# untitled.net
KiCad netlist of a schematic drawn in EAGLE
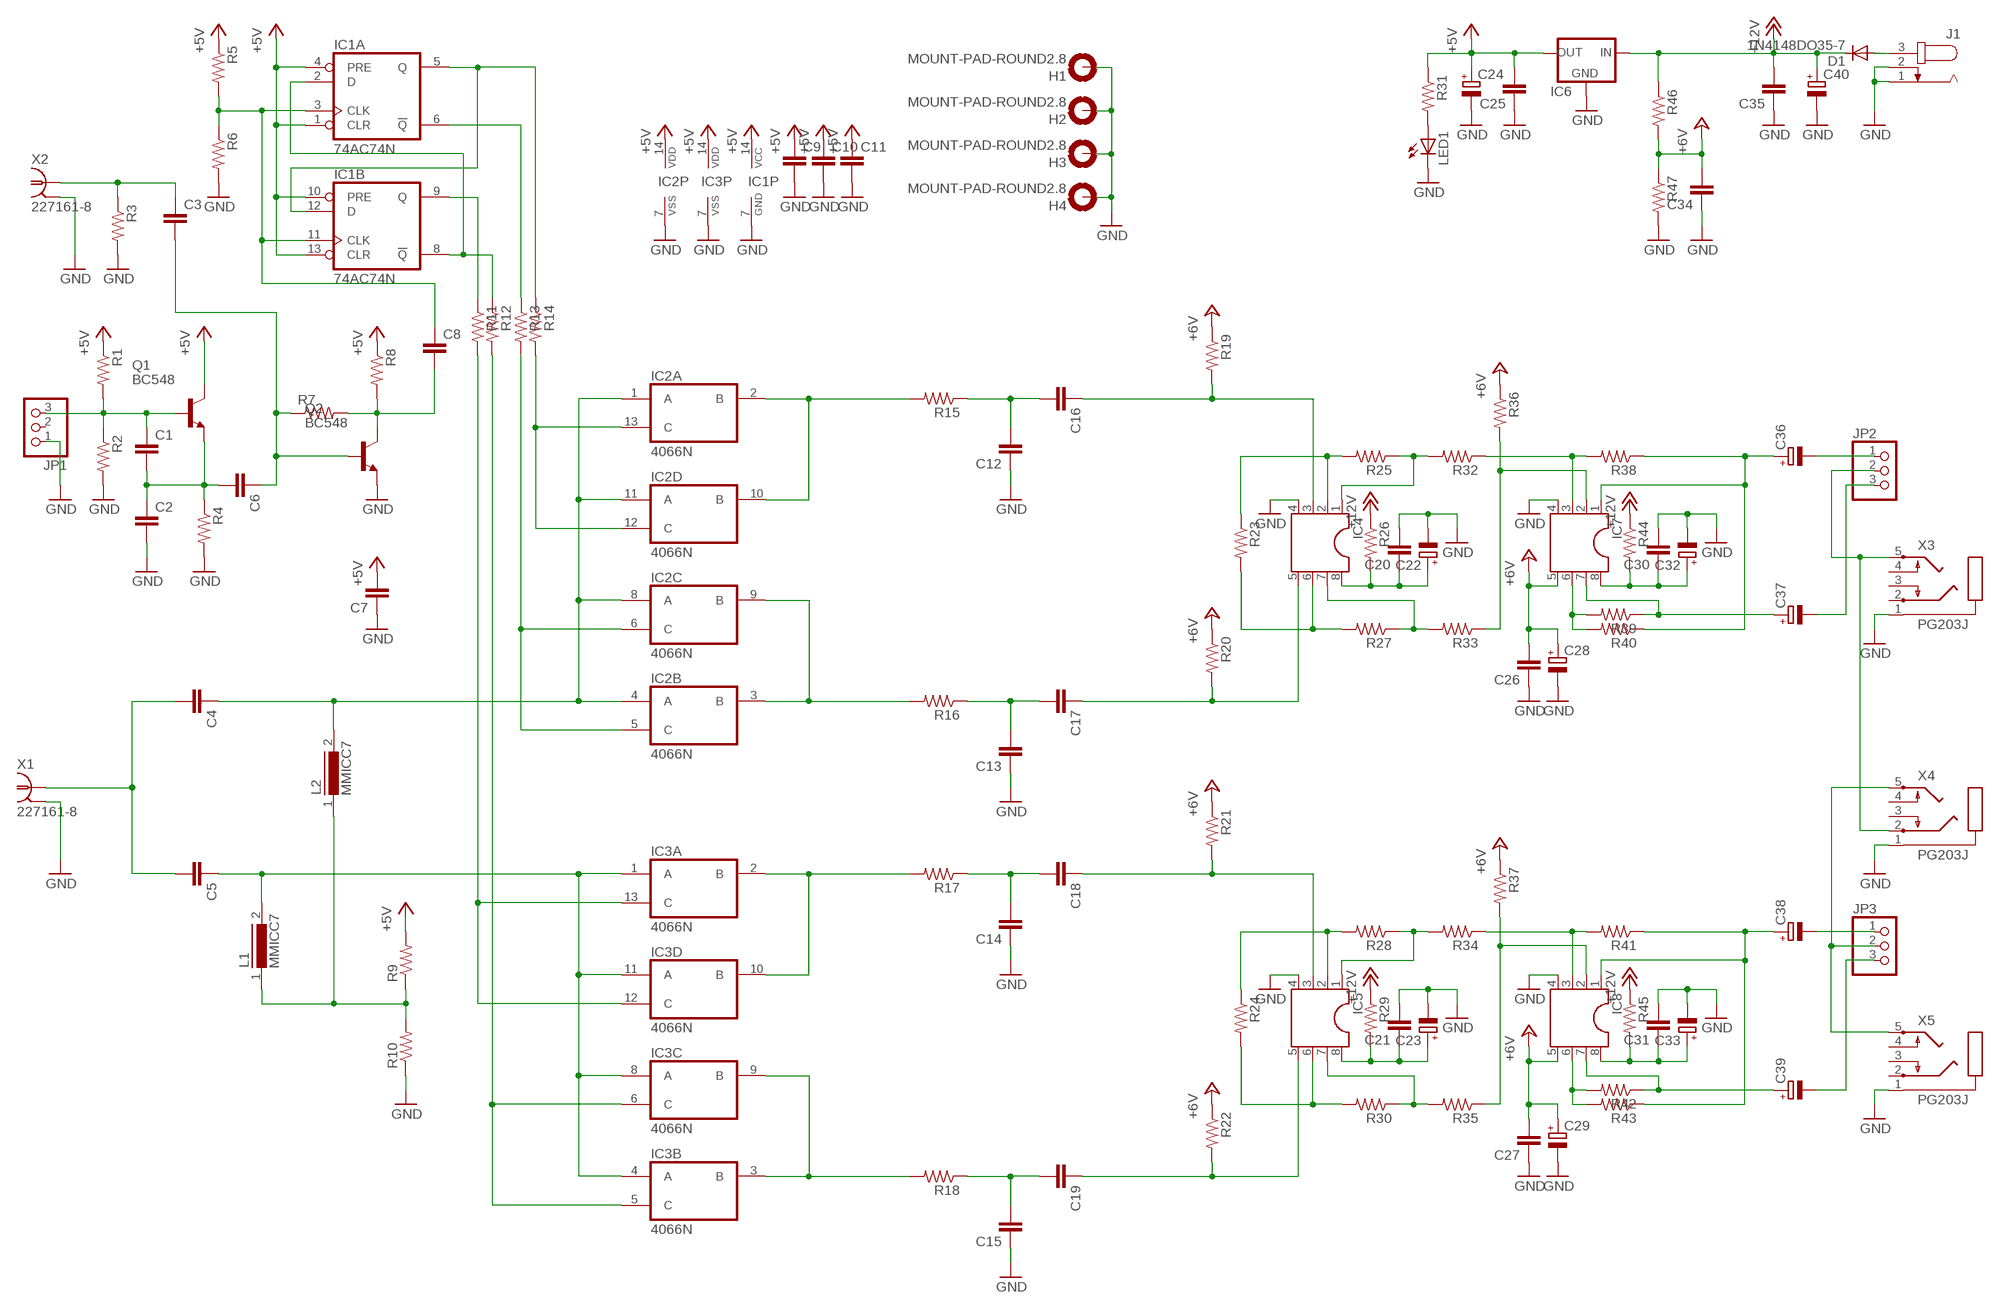
[diagram p0: schematic, sheet 1]

(export (version "E")
  (design (tool "Eeschema 10.0.6"))
  (components
    (comp (ref "C1")
      (value "C-EU025-025X050")
      (footprint "eagle-import:C025-025X050")
      (libsource (lib "eagle-import") (part "C-EU025-025X050"))
    )
    (comp (ref "C2")
      (value "C-EU025-025X050")
      (footprint "eagle-import:C025-025X050")
      (libsource (lib "eagle-import") (part "C-EU025-025X050"))
    )
    (comp (ref "C3")
      (value "C-EU050-025X075")
      (footprint "eagle-import:C050-025X075")
      (libsource (lib "eagle-import") (part "C-EU050-025X075"))
    )
    (comp (ref "C4")
      (value "C-EU050-025X075")
      (footprint "eagle-import:C050-025X075")
      (libsource (lib "eagle-import") (part "C-EU050-025X075"))
    )
    (comp (ref "C5")
      (value "C-EU050-025X075")
      (footprint "eagle-import:C050-025X075")
      (libsource (lib "eagle-import") (part "C-EU050-025X075"))
    )
    (comp (ref "C6")
      (value "C-EU050-025X075")
      (footprint "eagle-import:C050-025X075")
      (libsource (lib "eagle-import") (part "C-EU050-025X075"))
    )
    (comp (ref "C7")
      (value "C-EU050-025X075")
      (footprint "eagle-import:C050-025X075")
      (libsource (lib "eagle-import") (part "C-EU050-025X075"))
    )
    (comp (ref "C8")
      (value "C-EU075-032X103")
      (footprint "eagle-import:C075-032X103")
      (libsource (lib "eagle-import") (part "C-EU075-032X103"))
    )
    (comp (ref "C9")
      (value "C-EU050-025X075")
      (footprint "eagle-import:C050-025X075")
      (libsource (lib "eagle-import") (part "C-EU050-025X075"))
    )
    (comp (ref "C10")
      (value "C-EU050-025X075")
      (footprint "eagle-import:C050-025X075")
      (libsource (lib "eagle-import") (part "C-EU050-025X075"))
    )
    (comp (ref "C11")
      (value "C-EU050-025X075")
      (footprint "eagle-import:C050-025X075")
      (libsource (lib "eagle-import") (part "C-EU050-025X075"))
    )
    (comp (ref "C12")
      (value "C-EU050-025X075")
      (footprint "eagle-import:C050-025X075")
      (libsource (lib "eagle-import") (part "C-EU050-025X075"))
    )
    (comp (ref "C13")
      (value "C-EU050-025X075")
      (footprint "eagle-import:C050-025X075")
      (libsource (lib "eagle-import") (part "C-EU050-025X075"))
    )
    (comp (ref "C14")
      (value "C-EU050-025X075")
      (footprint "eagle-import:C050-025X075")
      (libsource (lib "eagle-import") (part "C-EU050-025X075"))
    )
    (comp (ref "C15")
      (value "C-EU050-025X075")
      (footprint "eagle-import:C050-025X075")
      (libsource (lib "eagle-import") (part "C-EU050-025X075"))
    )
    (comp (ref "C16")
      (value "C-EU050-025X075")
      (footprint "eagle-import:C050-025X075")
      (libsource (lib "eagle-import") (part "C-EU050-025X075"))
    )
    (comp (ref "C17")
      (value "C-EU050-025X075")
      (footprint "eagle-import:C050-025X075")
      (libsource (lib "eagle-import") (part "C-EU050-025X075"))
    )
    (comp (ref "C18")
      (value "C-EU050-025X075")
      (footprint "eagle-import:C050-025X075")
      (libsource (lib "eagle-import") (part "C-EU050-025X075"))
    )
    (comp (ref "C19")
      (value "C-EU050-025X075")
      (footprint "eagle-import:C050-025X075")
      (libsource (lib "eagle-import") (part "C-EU050-025X075"))
    )
    (comp (ref "C20")
      (value "C-EU050-025X075")
      (footprint "eagle-import:C050-025X075")
      (libsource (lib "eagle-import") (part "C-EU050-025X075"))
    )
    (comp (ref "C21")
      (value "C-EU050-025X075")
      (footprint "eagle-import:C050-025X075")
      (libsource (lib "eagle-import") (part "C-EU050-025X075"))
    )
    (comp (ref "C22")
      (value "CPOL-EUE5-6")
      (footprint "eagle-import:E5-6")
      (libsource (lib "eagle-import") (part "CPOL-EUE5-6"))
    )
    (comp (ref "C23")
      (value "CPOL-EUE5-6")
      (footprint "eagle-import:E5-6")
      (libsource (lib "eagle-import") (part "CPOL-EUE5-6"))
    )
    (comp (ref "C24")
      (value "CPOL-EUE5-6")
      (footprint "eagle-import:E5-6")
      (libsource (lib "eagle-import") (part "CPOL-EUE5-6"))
    )
    (comp (ref "C25")
      (value "C-EU050-025X075")
      (footprint "eagle-import:C050-025X075")
      (libsource (lib "eagle-import") (part "C-EU050-025X075"))
    )
    (comp (ref "C26")
      (value "C-EU050-025X075")
      (footprint "eagle-import:C050-025X075")
      (libsource (lib "eagle-import") (part "C-EU050-025X075"))
    )
    (comp (ref "C27")
      (value "C-EU050-025X075")
      (footprint "eagle-import:C050-025X075")
      (libsource (lib "eagle-import") (part "C-EU050-025X075"))
    )
    (comp (ref "C28")
      (value "CPOL-EUE5-6")
      (footprint "eagle-import:E5-6")
      (libsource (lib "eagle-import") (part "CPOL-EUE5-6"))
    )
    (comp (ref "C29")
      (value "CPOL-EUE5-6")
      (footprint "eagle-import:E5-6")
      (libsource (lib "eagle-import") (part "CPOL-EUE5-6"))
    )
    (comp (ref "C30")
      (value "C-EU050-025X075")
      (footprint "eagle-import:C050-025X075")
      (libsource (lib "eagle-import") (part "C-EU050-025X075"))
    )
    (comp (ref "C31")
      (value "C-EU050-025X075")
      (footprint "eagle-import:C050-025X075")
      (libsource (lib "eagle-import") (part "C-EU050-025X075"))
    )
    (comp (ref "C32")
      (value "CPOL-EUE5-6")
      (footprint "eagle-import:E5-6")
      (libsource (lib "eagle-import") (part "CPOL-EUE5-6"))
    )
    (comp (ref "C33")
      (value "CPOL-EUE5-6")
      (footprint "eagle-import:E5-6")
      (libsource (lib "eagle-import") (part "CPOL-EUE5-6"))
    )
    (comp (ref "C34")
      (value "C-EU050-025X075")
      (footprint "eagle-import:C050-025X075")
      (libsource (lib "eagle-import") (part "C-EU050-025X075"))
    )
    (comp (ref "C35")
      (value "C-EU050-025X075")
      (footprint "eagle-import:C050-025X075")
      (libsource (lib "eagle-import") (part "C-EU050-025X075"))
    )
    (comp (ref "C36")
      (value "CPOL-EUE5-6")
      (footprint "eagle-import:E5-6")
      (libsource (lib "eagle-import") (part "CPOL-EUE5-6"))
    )
    (comp (ref "C37")
      (value "CPOL-EUE5-6")
      (footprint "eagle-import:E5-6")
      (libsource (lib "eagle-import") (part "CPOL-EUE5-6"))
    )
    (comp (ref "C38")
      (value "CPOL-EUE5-6")
      (footprint "eagle-import:E5-6")
      (libsource (lib "eagle-import") (part "CPOL-EUE5-6"))
    )
    (comp (ref "C39")
      (value "CPOL-EUE5-6")
      (footprint "eagle-import:E5-6")
      (libsource (lib "eagle-import") (part "CPOL-EUE5-6"))
    )
    (comp (ref "C40")
      (value "CPOL-EUE5-6")
      (footprint "eagle-import:E5-6")
      (libsource (lib "eagle-import") (part "CPOL-EUE5-6"))
    )
    (comp (ref "D1")
      (value "1N4148DO35-7")
      (footprint "eagle-import:DO35-7")
      (libsource (lib "eagle-import") (part "1N4148DO35-7"))
    )
    (comp (ref "H1")
      (value "MOUNT-PAD-ROUND2.8")
      (footprint "eagle-import:2,8-PAD")
      (libsource (lib "eagle-import") (part "MOUNT-PAD-ROUND2.8"))
    )
    (comp (ref "H2")
      (value "MOUNT-PAD-ROUND2.8")
      (footprint "eagle-import:2,8-PAD")
      (libsource (lib "eagle-import") (part "MOUNT-PAD-ROUND2.8"))
    )
    (comp (ref "H3")
      (value "MOUNT-PAD-ROUND2.8")
      (footprint "eagle-import:2,8-PAD")
      (libsource (lib "eagle-import") (part "MOUNT-PAD-ROUND2.8"))
    )
    (comp (ref "H4")
      (value "MOUNT-PAD-ROUND2.8")
      (footprint "eagle-import:2,8-PAD")
      (libsource (lib "eagle-import") (part "MOUNT-PAD-ROUND2.8"))
    )
    (comp (ref "IC1")
      (value "74AC74N")
      (footprint "eagle-import:DIL14")
      (libsource (lib "eagle-import") (part "7474NAC"))
    )
    (comp (ref "IC2")
      (value "4066N")
      (footprint "eagle-import:DIL14")
      (libsource (lib "eagle-import") (part "4066N"))
    )
    (comp (ref "IC3")
      (value "4066N")
      (footprint "eagle-import:DIL14")
      (libsource (lib "eagle-import") (part "4066N"))
    )
    (comp (ref "IC4")
      (value "DIL8")
      (footprint "eagle-import:DIL08")
      (libsource (lib "eagle-import") (part "DIL8"))
    )
    (comp (ref "IC5")
      (value "DIL8")
      (footprint "eagle-import:DIL08")
      (libsource (lib "eagle-import") (part "DIL8"))
    )
    (comp (ref "IC6")
      (value "78XXS")
      (footprint "eagle-import:78XXS")
      (libsource (lib "eagle-import") (part "78XXS"))
    )
    (comp (ref "IC7")
      (value "DIL8")
      (footprint "eagle-import:DIL08")
      (libsource (lib "eagle-import") (part "DIL8"))
    )
    (comp (ref "IC8")
      (value "DIL8")
      (footprint "eagle-import:DIL08")
      (libsource (lib "eagle-import") (part "DIL8"))
    )
    (comp (ref "J1")
      (value "JACK-PLUG0")
      (footprint "eagle-import:SPC4077")
      (libsource (lib "eagle-import") (part "JACK-PLUG0"))
    )
    (comp (ref "JP1")
      (value "PINHD-1X3")
      (footprint "eagle-import:1X03")
      (libsource (lib "eagle-import") (part "PINHD-1X3"))
    )
    (comp (ref "JP2")
      (value "PINHD-1X3")
      (footprint "eagle-import:1X03")
      (libsource (lib "eagle-import") (part "PINHD-1X3"))
    )
    (comp (ref "JP3")
      (value "PINHD-1X3")
      (footprint "eagle-import:1X03")
      (libsource (lib "eagle-import") (part "PINHD-1X3"))
    )
    (comp (ref "L1")
      (value "MMICC7")
      (footprint "eagle-import:MMICC7")
      (libsource (lib "eagle-import") (part "MMICC7"))
    )
    (comp (ref "L2")
      (value "MMICC7")
      (footprint "eagle-import:MMICC7")
      (libsource (lib "eagle-import") (part "MMICC7"))
    )
    (comp (ref "LED1")
      (value "LED3MM")
      (footprint "eagle-import:LED3MM")
      (libsource (lib "eagle-import") (part "LED3MM"))
    )
    (comp (ref "Q1")
      (value "BC548")
      (footprint "eagle-import:TO92-EBC")
      (libsource (lib "eagle-import") (part "BC548"))
    )
    (comp (ref "Q2")
      (value "BC548")
      (footprint "eagle-import:TO92-EBC")
      (libsource (lib "eagle-import") (part "BC548"))
    )
    (comp (ref "R1")
      (value "R-US_0207/7")
      (footprint "eagle-import:0207_7")
      (libsource (lib "eagle-import") (part "R-US_0207/7"))
    )
    (comp (ref "R2")
      (value "R-US_0207/7")
      (footprint "eagle-import:0207_7")
      (libsource (lib "eagle-import") (part "R-US_0207/7"))
    )
    (comp (ref "R3")
      (value "R-US_0207/7")
      (footprint "eagle-import:0207_7")
      (libsource (lib "eagle-import") (part "R-US_0207/7"))
    )
    (comp (ref "R4")
      (value "R-US_0207/7")
      (footprint "eagle-import:0207_7")
      (libsource (lib "eagle-import") (part "R-US_0207/7"))
    )
    (comp (ref "R5")
      (value "R-US_0207/7")
      (footprint "eagle-import:0207_7")
      (libsource (lib "eagle-import") (part "R-US_0207/7"))
    )
    (comp (ref "R6")
      (value "R-US_0207/7")
      (footprint "eagle-import:0207_7")
      (libsource (lib "eagle-import") (part "R-US_0207/7"))
    )
    (comp (ref "R7")
      (value "R-US_0207/7")
      (footprint "eagle-import:0207_7")
      (libsource (lib "eagle-import") (part "R-US_0207/7"))
    )
    (comp (ref "R8")
      (value "R-US_0207/7")
      (footprint "eagle-import:0207_7")
      (libsource (lib "eagle-import") (part "R-US_0207/7"))
    )
    (comp (ref "R9")
      (value "R-US_0207/7")
      (footprint "eagle-import:0207_7")
      (libsource (lib "eagle-import") (part "R-US_0207/7"))
    )
    (comp (ref "R10")
      (value "R-US_0207/7")
      (footprint "eagle-import:0207_7")
      (libsource (lib "eagle-import") (part "R-US_0207/7"))
    )
    (comp (ref "R11")
      (value "R-US_0207/7")
      (footprint "eagle-import:0207_7")
      (libsource (lib "eagle-import") (part "R-US_0207/7"))
    )
    (comp (ref "R12")
      (value "R-US_0207/7")
      (footprint "eagle-import:0207_7")
      (libsource (lib "eagle-import") (part "R-US_0207/7"))
    )
    (comp (ref "R13")
      (value "R-US_0207/7")
      (footprint "eagle-import:0207_7")
      (libsource (lib "eagle-import") (part "R-US_0207/7"))
    )
    (comp (ref "R14")
      (value "R-US_0207/7")
      (footprint "eagle-import:0207_7")
      (libsource (lib "eagle-import") (part "R-US_0207/7"))
    )
    (comp (ref "R15")
      (value "R-US_0207/7")
      (footprint "eagle-import:0207_7")
      (libsource (lib "eagle-import") (part "R-US_0207/7"))
    )
    (comp (ref "R16")
      (value "R-US_0207/7")
      (footprint "eagle-import:0207_7")
      (libsource (lib "eagle-import") (part "R-US_0207/7"))
    )
    (comp (ref "R17")
      (value "R-US_0207/7")
      (footprint "eagle-import:0207_7")
      (libsource (lib "eagle-import") (part "R-US_0207/7"))
    )
    (comp (ref "R18")
      (value "R-US_0207/7")
      (footprint "eagle-import:0207_7")
      (libsource (lib "eagle-import") (part "R-US_0207/7"))
    )
    (comp (ref "R19")
      (value "R-US_0207/7")
      (footprint "eagle-import:0207_7")
      (libsource (lib "eagle-import") (part "R-US_0207/7"))
    )
    (comp (ref "R20")
      (value "R-US_0207/7")
      (footprint "eagle-import:0207_7")
      (libsource (lib "eagle-import") (part "R-US_0207/7"))
    )
    (comp (ref "R21")
      (value "R-US_0207/7")
      (footprint "eagle-import:0207_7")
      (libsource (lib "eagle-import") (part "R-US_0207/7"))
    )
    (comp (ref "R22")
      (value "R-US_0207/7")
      (footprint "eagle-import:0207_7")
      (libsource (lib "eagle-import") (part "R-US_0207/7"))
    )
    (comp (ref "R23")
      (value "R-US_0207/7")
      (footprint "eagle-import:0207_7")
      (libsource (lib "eagle-import") (part "R-US_0207/7"))
    )
    (comp (ref "R24")
      (value "R-US_0207/7")
      (footprint "eagle-import:0207_7")
      (libsource (lib "eagle-import") (part "R-US_0207/7"))
    )
    (comp (ref "R25")
      (value "R-US_0207/7")
      (footprint "eagle-import:0207_7")
      (libsource (lib "eagle-import") (part "R-US_0207/7"))
    )
    (comp (ref "R26")
      (value "R-US_0207/7")
      (footprint "eagle-import:0207_7")
      (libsource (lib "eagle-import") (part "R-US_0207/7"))
    )
    (comp (ref "R27")
      (value "R-US_0207/7")
      (footprint "eagle-import:0207_7")
      (libsource (lib "eagle-import") (part "R-US_0207/7"))
    )
    (comp (ref "R28")
      (value "R-US_0207/7")
      (footprint "eagle-import:0207_7")
      (libsource (lib "eagle-import") (part "R-US_0207/7"))
    )
    (comp (ref "R29")
      (value "R-US_0207/7")
      (footprint "eagle-import:0207_7")
      (libsource (lib "eagle-import") (part "R-US_0207/7"))
    )
    (comp (ref "R30")
      (value "R-US_0207/7")
      (footprint "eagle-import:0207_7")
      (libsource (lib "eagle-import") (part "R-US_0207/7"))
    )
    (comp (ref "R31")
      (value "R-US_0207/7")
      (footprint "eagle-import:0207_7")
      (libsource (lib "eagle-import") (part "R-US_0207/7"))
    )
    (comp (ref "R32")
      (value "R-US_0207/7")
      (footprint "eagle-import:0207_7")
      (libsource (lib "eagle-import") (part "R-US_0207/7"))
    )
    (comp (ref "R33")
      (value "R-US_0207/7")
      (footprint "eagle-import:0207_7")
      (libsource (lib "eagle-import") (part "R-US_0207/7"))
    )
    (comp (ref "R34")
      (value "R-US_0207/7")
      (footprint "eagle-import:0207_7")
      (libsource (lib "eagle-import") (part "R-US_0207/7"))
    )
    (comp (ref "R35")
      (value "R-US_0207/7")
      (footprint "eagle-import:0207_7")
      (libsource (lib "eagle-import") (part "R-US_0207/7"))
    )
    (comp (ref "R36")
      (value "R-US_0207/7")
      (footprint "eagle-import:0207_7")
      (libsource (lib "eagle-import") (part "R-US_0207/7"))
    )
    (comp (ref "R37")
      (value "R-US_0207/7")
      (footprint "eagle-import:0207_7")
      (libsource (lib "eagle-import") (part "R-US_0207/7"))
    )
    (comp (ref "R38")
      (value "R-US_0207/7")
      (footprint "eagle-import:0207_7")
      (libsource (lib "eagle-import") (part "R-US_0207/7"))
    )
    (comp (ref "R39")
      (value "R-US_0207/7")
      (footprint "eagle-import:0207_7")
      (libsource (lib "eagle-import") (part "R-US_0207/7"))
    )
    (comp (ref "R40")
      (value "R-US_0207/7")
      (footprint "eagle-import:0207_7")
      (libsource (lib "eagle-import") (part "R-US_0207/7"))
    )
    (comp (ref "R41")
      (value "R-US_0207/7")
      (footprint "eagle-import:0207_7")
      (libsource (lib "eagle-import") (part "R-US_0207/7"))
    )
    (comp (ref "R42")
      (value "R-US_0207/7")
      (footprint "eagle-import:0207_7")
      (libsource (lib "eagle-import") (part "R-US_0207/7"))
    )
    (comp (ref "R43")
      (value "R-US_0207/7")
      (footprint "eagle-import:0207_7")
      (libsource (lib "eagle-import") (part "R-US_0207/7"))
    )
    (comp (ref "R44")
      (value "R-US_0207/7")
      (footprint "eagle-import:0207_7")
      (libsource (lib "eagle-import") (part "R-US_0207/7"))
    )
    (comp (ref "R45")
      (value "R-US_0207/7")
      (footprint "eagle-import:0207_7")
      (libsource (lib "eagle-import") (part "R-US_0207/7"))
    )
    (comp (ref "R46")
      (value "R-US_0207/7")
      (footprint "eagle-import:0207_7")
      (libsource (lib "eagle-import") (part "R-US_0207/7"))
    )
    (comp (ref "R47")
      (value "R-US_0207/7")
      (footprint "eagle-import:0207_7")
      (libsource (lib "eagle-import") (part "R-US_0207/7"))
    )
    (comp (ref "X1")
      (value "227161-8")
      (footprint "eagle-import:AMP_227161")
      (libsource (lib "eagle-import") (part "?227161-8"))
    )
    (comp (ref "X2")
      (value "227161-8")
      (footprint "eagle-import:AMP_227161")
      (libsource (lib "eagle-import") (part "?227161-8"))
    )
    (comp (ref "X3")
      (value "PG203J")
      (footprint "eagle-import:PG203J")
      (libsource (lib "eagle-import") (part "PG203J"))
    )
    (comp (ref "X4")
      (value "PG203J")
      (footprint "eagle-import:PG203J")
      (libsource (lib "eagle-import") (part "PG203J"))
    )
    (comp (ref "X5")
      (value "PG203J")
      (footprint "eagle-import:PG203J")
      (libsource (lib "eagle-import") (part "PG203J"))
    )
  )
  (nets
    (net (code "1") (name "+5V") (class "Default")
      (node (ref "C10") (pin "1") (pinfunction "1_1") (pintype "passive"))
      (node (ref "C11") (pin "1") (pinfunction "1_1") (pintype "passive"))
      (node (ref "C24") (pin "+") (pinfunction "+_+") (pintype "passive"))
      (node (ref "C25") (pin "2") (pinfunction "2_2") (pintype "passive"))
      (node (ref "C7") (pin "2") (pinfunction "2_2") (pintype "passive"))
      (node (ref "C9") (pin "1") (pinfunction "1_1") (pintype "passive"))
      (node (ref "IC1") (pin "1") (pinfunction "CLR_1") (pintype "input"))
      (node (ref "IC1") (pin "10") (pinfunction "PRE_10") (pintype "input"))
      (node (ref "IC1") (pin "13") (pinfunction "CLR_13") (pintype "input"))
      (node (ref "IC1") (pin "14") (pinfunction "VCC_14") (pintype "power_in"))
      (node (ref "IC1") (pin "4") (pinfunction "PRE_4") (pintype "input"))
      (node (ref "IC2") (pin "14") (pinfunction "VDD_14") (pintype "power_in"))
      (node (ref "IC3") (pin "14") (pinfunction "VDD_14") (pintype "power_in"))
      (node (ref "IC6") (pin "OUT") (pinfunction "OUT_OUT") (pintype "passive"))
      (node (ref "Q1") (pin "C") (pinfunction "C_C") (pintype "passive"))
      (node (ref "R1") (pin "1") (pinfunction "1_1") (pintype "passive"))
      (node (ref "R31") (pin "1") (pinfunction "1_1") (pintype "passive"))
      (node (ref "R5") (pin "1") (pinfunction "1_1") (pintype "passive"))
      (node (ref "R8") (pin "1") (pinfunction "1_1") (pintype "passive"))
      (node (ref "R9") (pin "2") (pinfunction "2_2") (pintype "passive"))
    )
    (net (code "2") (name "+6V") (class "Default")
      (node (ref "C26") (pin "2") (pinfunction "2_2") (pintype "passive"))
      (node (ref "C27") (pin "2") (pinfunction "2_2") (pintype "passive"))
      (node (ref "C28") (pin "+") (pinfunction "+_+") (pintype "passive"))
      (node (ref "C29") (pin "+") (pinfunction "+_+") (pintype "passive"))
      (node (ref "C34") (pin "2") (pinfunction "2_2") (pintype "passive"))
      (node (ref "IC7") (pin "5") (pinfunction "5_5") (pintype "passive"))
      (node (ref "IC8") (pin "5") (pinfunction "5_5") (pintype "passive"))
      (node (ref "R19") (pin "1") (pinfunction "1_1") (pintype "passive"))
      (node (ref "R20") (pin "1") (pinfunction "1_1") (pintype "passive"))
      (node (ref "R21") (pin "1") (pinfunction "1_1") (pintype "passive"))
      (node (ref "R22") (pin "1") (pinfunction "1_1") (pintype "passive"))
      (node (ref "R36") (pin "1") (pinfunction "1_1") (pintype "passive"))
      (node (ref "R37") (pin "1") (pinfunction "1_1") (pintype "passive"))
      (node (ref "R46") (pin "2") (pinfunction "2_2") (pintype "passive"))
      (node (ref "R47") (pin "1") (pinfunction "1_1") (pintype "passive"))
    )
    (net (code "3") (name "+12V") (class "Default")
      (node (ref "C35") (pin "2") (pinfunction "2_2") (pintype "passive"))
      (node (ref "C40") (pin "+") (pinfunction "+_+") (pintype "passive"))
      (node (ref "D1") (pin "C") (pinfunction "C_C") (pintype "passive"))
      (node (ref "IC6") (pin "IN") (pinfunction "IN_IN") (pintype "input"))
      (node (ref "R26") (pin "1") (pinfunction "1_1") (pintype "passive"))
      (node (ref "R29") (pin "1") (pinfunction "1_1") (pintype "passive"))
      (node (ref "R44") (pin "1") (pinfunction "1_1") (pintype "passive"))
      (node (ref "R45") (pin "1") (pinfunction "1_1") (pintype "passive"))
      (node (ref "R46") (pin "1") (pinfunction "1_1") (pintype "passive"))
    )
    (net (code "4") (name "GND") (class "Default")
      (node (ref "C10") (pin "2") (pinfunction "2_2") (pintype "passive"))
      (node (ref "C11") (pin "2") (pinfunction "2_2") (pintype "passive"))
      (node (ref "C12") (pin "1") (pinfunction "1_1") (pintype "passive"))
      (node (ref "C13") (pin "1") (pinfunction "1_1") (pintype "passive"))
      (node (ref "C14") (pin "1") (pinfunction "1_1") (pintype "passive"))
      (node (ref "C15") (pin "1") (pinfunction "1_1") (pintype "passive"))
      (node (ref "C2") (pin "2") (pinfunction "2_2") (pintype "passive"))
      (node (ref "C20") (pin "2") (pinfunction "2_2") (pintype "passive"))
      (node (ref "C21") (pin "2") (pinfunction "2_2") (pintype "passive"))
      (node (ref "C22") (pin "-") (pinfunction "-_-") (pintype "passive"))
      (node (ref "C23") (pin "-") (pinfunction "-_-") (pintype "passive"))
      (node (ref "C24") (pin "-") (pinfunction "-_-") (pintype "passive"))
      (node (ref "C25") (pin "1") (pinfunction "1_1") (pintype "passive"))
      (node (ref "C26") (pin "1") (pinfunction "1_1") (pintype "passive"))
      (node (ref "C27") (pin "1") (pinfunction "1_1") (pintype "passive"))
      (node (ref "C28") (pin "-") (pinfunction "-_-") (pintype "passive"))
      (node (ref "C29") (pin "-") (pinfunction "-_-") (pintype "passive"))
      (node (ref "C30") (pin "2") (pinfunction "2_2") (pintype "passive"))
      (node (ref "C31") (pin "2") (pinfunction "2_2") (pintype "passive"))
      (node (ref "C32") (pin "-") (pinfunction "-_-") (pintype "passive"))
      (node (ref "C33") (pin "-") (pinfunction "-_-") (pintype "passive"))
      (node (ref "C34") (pin "1") (pinfunction "1_1") (pintype "passive"))
      (node (ref "C35") (pin "1") (pinfunction "1_1") (pintype "passive"))
      (node (ref "C40") (pin "-") (pinfunction "-_-") (pintype "passive"))
      (node (ref "C7") (pin "1") (pinfunction "1_1") (pintype "passive"))
      (node (ref "C9") (pin "2") (pinfunction "2_2") (pintype "passive"))
      (node (ref "H1") (pin "B2,8") (pinfunction "MOUNT_B2,8") (pintype "passive"))
      (node (ref "H2") (pin "B2,8") (pinfunction "MOUNT_B2,8") (pintype "passive"))
      (node (ref "H3") (pin "B2,8") (pinfunction "MOUNT_B2,8") (pintype "passive"))
      (node (ref "H4") (pin "B2,8") (pinfunction "MOUNT_B2,8") (pintype "passive"))
      (node (ref "IC1") (pin "7") (pinfunction "GND_7") (pintype "power_in"))
      (node (ref "IC2") (pin "7") (pinfunction "VSS_7") (pintype "power_in"))
      (node (ref "IC3") (pin "7") (pinfunction "VSS_7") (pintype "power_in"))
      (node (ref "IC4") (pin "4") (pinfunction "4_4") (pintype "passive"))
      (node (ref "IC5") (pin "4") (pinfunction "4_4") (pintype "passive"))
      (node (ref "IC6") (pin "GND") (pinfunction "GND_GND") (pintype "input"))
      (node (ref "IC7") (pin "4") (pinfunction "4_4") (pintype "passive"))
      (node (ref "IC8") (pin "4") (pinfunction "4_4") (pintype "passive"))
      (node (ref "J1") (pin "1") (pinfunction "1_1") (pintype "passive"))
      (node (ref "J1") (pin "2") (pinfunction "2_2") (pintype "passive"))
      (node (ref "JP1") (pin "1") (pinfunction "1_1") (pintype "passive"))
      (node (ref "LED1") (pin "K") (pinfunction "C_K") (pintype "passive"))
      (node (ref "Q2") (pin "E") (pinfunction "E_E") (pintype "passive"))
      (node (ref "R10") (pin "1") (pinfunction "1_1") (pintype "passive"))
      (node (ref "R2") (pin "2") (pinfunction "2_2") (pintype "passive"))
      (node (ref "R3") (pin "2") (pinfunction "2_2") (pintype "passive"))
      (node (ref "R4") (pin "2") (pinfunction "2_2") (pintype "passive"))
      (node (ref "R47") (pin "2") (pinfunction "2_2") (pintype "passive"))
      (node (ref "R6") (pin "2") (pinfunction "2_2") (pintype "passive"))
      (node (ref "X1") (pin "2") (pinfunction "2_2") (pintype "passive"))
      (node (ref "X2") (pin "2") (pinfunction "2_2") (pintype "passive"))
      (node (ref "X3") (pin "1") (pinfunction "1_1") (pintype "passive"))
      (node (ref "X4") (pin "1") (pinfunction "1_1") (pintype "passive"))
      (node (ref "X5") (pin "1") (pinfunction "1_1") (pintype "passive"))
    )
    (net (code "5") (name "Net-(C1-Pad1)") (class "Default")
      (node (ref "C1") (pin "1") (pinfunction "1_1") (pintype "passive"))
      (node (ref "JP1") (pin "3") (pinfunction "3_3") (pintype "passive"))
      (node (ref "Q1") (pin "B") (pinfunction "B_B") (pintype "passive"))
      (node (ref "R1") (pin "2") (pinfunction "2_2") (pintype "passive"))
      (node (ref "R2") (pin "1") (pinfunction "1_1") (pintype "passive"))
    )
    (net (code "6") (name "Net-(C1-Pad2)") (class "Default")
      (node (ref "C1") (pin "2") (pinfunction "2_2") (pintype "passive"))
      (node (ref "C2") (pin "1") (pinfunction "1_1") (pintype "passive"))
      (node (ref "C6") (pin "2") (pinfunction "2_2") (pintype "passive"))
      (node (ref "Q1") (pin "E") (pinfunction "E_E") (pintype "passive"))
      (node (ref "R4") (pin "1") (pinfunction "1_1") (pintype "passive"))
    )
    (net (code "7") (name "Net-(C3-Pad1)") (class "Default")
      (node (ref "C3") (pin "1") (pinfunction "1_1") (pintype "passive"))
      (node (ref "R3") (pin "1") (pinfunction "1_1") (pintype "passive"))
      (node (ref "X2") (pin "1") (pinfunction "1_1") (pintype "passive"))
    )
    (net (code "8") (name "Net-(C3-Pad2)") (class "Default")
      (node (ref "C3") (pin "2") (pinfunction "2_2") (pintype "passive"))
      (node (ref "C6") (pin "1") (pinfunction "1_1") (pintype "passive"))
      (node (ref "Q2") (pin "B") (pinfunction "B_B") (pintype "passive"))
      (node (ref "R7") (pin "1") (pinfunction "1_1") (pintype "passive"))
    )
    (net (code "9") (name "Net-(C4-Pad2)") (class "Default")
      (node (ref "C4") (pin "2") (pinfunction "2_2") (pintype "passive"))
      (node (ref "C5") (pin "2") (pinfunction "2_2") (pintype "passive"))
      (node (ref "X1") (pin "1") (pinfunction "1_1") (pintype "passive"))
    )
    (net (code "10") (name "Net-(C8-Pad2)") (class "Default")
      (node (ref "C8") (pin "2") (pinfunction "2_2") (pintype "passive"))
      (node (ref "Q2") (pin "C") (pinfunction "C_C") (pintype "passive"))
      (node (ref "R7") (pin "2") (pinfunction "2_2") (pintype "passive"))
      (node (ref "R8") (pin "2") (pinfunction "2_2") (pintype "passive"))
    )
    (net (code "11") (name "Net-(C12-Pad2)") (class "Default")
      (node (ref "C12") (pin "2") (pinfunction "2_2") (pintype "passive"))
      (node (ref "C16") (pin "2") (pinfunction "2_2") (pintype "passive"))
      (node (ref "R15") (pin "1") (pinfunction "1_1") (pintype "passive"))
    )
    (net (code "12") (name "Net-(C13-Pad2)") (class "Default")
      (node (ref "C13") (pin "2") (pinfunction "2_2") (pintype "passive"))
      (node (ref "C17") (pin "2") (pinfunction "2_2") (pintype "passive"))
      (node (ref "R16") (pin "1") (pinfunction "1_1") (pintype "passive"))
    )
    (net (code "13") (name "Net-(C14-Pad2)") (class "Default")
      (node (ref "C14") (pin "2") (pinfunction "2_2") (pintype "passive"))
      (node (ref "C18") (pin "2") (pinfunction "2_2") (pintype "passive"))
      (node (ref "R17") (pin "1") (pinfunction "1_1") (pintype "passive"))
    )
    (net (code "14") (name "Net-(C15-Pad2)") (class "Default")
      (node (ref "C15") (pin "2") (pinfunction "2_2") (pintype "passive"))
      (node (ref "C19") (pin "2") (pinfunction "2_2") (pintype "passive"))
      (node (ref "R18") (pin "1") (pinfunction "1_1") (pintype "passive"))
    )
    (net (code "15") (name "Net-(C16-Pad1)") (class "Default")
      (node (ref "C16") (pin "1") (pinfunction "1_1") (pintype "passive"))
      (node (ref "IC4") (pin "3") (pinfunction "3_3") (pintype "passive"))
      (node (ref "R19") (pin "2") (pinfunction "2_2") (pintype "passive"))
    )
    (net (code "16") (name "Net-(C17-Pad1)") (class "Default")
      (node (ref "C17") (pin "1") (pinfunction "1_1") (pintype "passive"))
      (node (ref "IC4") (pin "5") (pinfunction "5_5") (pintype "passive"))
      (node (ref "R20") (pin "2") (pinfunction "2_2") (pintype "passive"))
    )
    (net (code "17") (name "Net-(C18-Pad1)") (class "Default")
      (node (ref "C18") (pin "1") (pinfunction "1_1") (pintype "passive"))
      (node (ref "IC5") (pin "3") (pinfunction "3_3") (pintype "passive"))
      (node (ref "R21") (pin "2") (pinfunction "2_2") (pintype "passive"))
    )
    (net (code "18") (name "Net-(C19-Pad1)") (class "Default")
      (node (ref "C19") (pin "1") (pinfunction "1_1") (pintype "passive"))
      (node (ref "IC5") (pin "5") (pinfunction "5_5") (pintype "passive"))
      (node (ref "R22") (pin "2") (pinfunction "2_2") (pintype "passive"))
    )
    (net (code "19") (name "Net-(C20-Pad1)") (class "Default")
      (node (ref "C20") (pin "1") (pinfunction "1_1") (pintype "passive"))
      (node (ref "C22") (pin "+") (pinfunction "+_+") (pintype "passive"))
      (node (ref "IC4") (pin "8") (pinfunction "8_8") (pintype "passive"))
      (node (ref "R26") (pin "2") (pinfunction "2_2") (pintype "passive"))
    )
    (net (code "20") (name "Net-(C21-Pad1)") (class "Default")
      (node (ref "C21") (pin "1") (pinfunction "1_1") (pintype "passive"))
      (node (ref "C23") (pin "+") (pinfunction "+_+") (pintype "passive"))
      (node (ref "IC5") (pin "8") (pinfunction "8_8") (pintype "passive"))
      (node (ref "R29") (pin "2") (pinfunction "2_2") (pintype "passive"))
    )
    (net (code "21") (name "Net-(C30-Pad1)") (class "Default")
      (node (ref "C30") (pin "1") (pinfunction "1_1") (pintype "passive"))
      (node (ref "C32") (pin "+") (pinfunction "+_+") (pintype "passive"))
      (node (ref "IC7") (pin "8") (pinfunction "8_8") (pintype "passive"))
      (node (ref "R44") (pin "2") (pinfunction "2_2") (pintype "passive"))
    )
    (net (code "22") (name "Net-(C31-Pad1)") (class "Default")
      (node (ref "C31") (pin "1") (pinfunction "1_1") (pintype "passive"))
      (node (ref "C33") (pin "+") (pinfunction "+_+") (pintype "passive"))
      (node (ref "IC8") (pin "8") (pinfunction "8_8") (pintype "passive"))
      (node (ref "R45") (pin "2") (pinfunction "2_2") (pintype "passive"))
    )
    (net (code "23") (name "Net-(C36-Pad+)") (class "Default")
      (node (ref "C36") (pin "+") (pinfunction "+_+") (pintype "passive"))
      (node (ref "IC7") (pin "1") (pinfunction "1_1") (pintype "passive"))
      (node (ref "R38") (pin "1") (pinfunction "1_1") (pintype "passive"))
      (node (ref "R40") (pin "1") (pinfunction "1_1") (pintype "passive"))
    )
    (net (code "24") (name "Net-(C36-Pad-)") (class "Default")
      (node (ref "C36") (pin "-") (pinfunction "-_-") (pintype "passive"))
      (node (ref "JP2") (pin "1") (pinfunction "1_1") (pintype "passive"))
    )
    (net (code "25") (name "Net-(C37-Pad+)") (class "Default")
      (node (ref "C37") (pin "+") (pinfunction "+_+") (pintype "passive"))
      (node (ref "IC7") (pin "7") (pinfunction "7_7") (pintype "passive"))
      (node (ref "R39") (pin "1") (pinfunction "1_1") (pintype "passive"))
    )
    (net (code "26") (name "Net-(C37-Pad-)") (class "Default")
      (node (ref "C37") (pin "-") (pinfunction "-_-") (pintype "passive"))
      (node (ref "JP2") (pin "3") (pinfunction "3_3") (pintype "passive"))
    )
    (net (code "27") (name "Net-(C38-Pad+)") (class "Default")
      (node (ref "C38") (pin "+") (pinfunction "+_+") (pintype "passive"))
      (node (ref "IC8") (pin "1") (pinfunction "1_1") (pintype "passive"))
      (node (ref "R41") (pin "1") (pinfunction "1_1") (pintype "passive"))
      (node (ref "R43") (pin "1") (pinfunction "1_1") (pintype "passive"))
    )
    (net (code "28") (name "Net-(C38-Pad-)") (class "Default")
      (node (ref "C38") (pin "-") (pinfunction "-_-") (pintype "passive"))
      (node (ref "JP3") (pin "1") (pinfunction "1_1") (pintype "passive"))
    )
    (net (code "29") (name "Net-(C39-Pad+)") (class "Default")
      (node (ref "C39") (pin "+") (pinfunction "+_+") (pintype "passive"))
      (node (ref "IC8") (pin "7") (pinfunction "7_7") (pintype "passive"))
      (node (ref "R42") (pin "1") (pinfunction "1_1") (pintype "passive"))
    )
    (net (code "30") (name "Net-(C39-Pad-)") (class "Default")
      (node (ref "C39") (pin "-") (pinfunction "-_-") (pintype "passive"))
      (node (ref "JP3") (pin "3") (pinfunction "3_3") (pintype "passive"))
    )
    (net (code "31") (name "Net-(D1-PadA)") (class "Default")
      (node (ref "D1") (pin "A") (pinfunction "A_A") (pintype "passive"))
      (node (ref "J1") (pin "3") (pinfunction "3_3") (pintype "passive"))
    )
    (net (code "32") (name "Net-(IC1A-CLK)") (class "Default")
      (node (ref "C8") (pin "1") (pinfunction "1_1") (pintype "passive"))
      (node (ref "IC1") (pin "11") (pinfunction "CLK_11") (pintype "input"))
      (node (ref "IC1") (pin "3") (pinfunction "CLK_3") (pintype "input"))
      (node (ref "R5") (pin "2") (pinfunction "2_2") (pintype "passive"))
      (node (ref "R6") (pin "1") (pinfunction "1_1") (pintype "passive"))
    )
    (net (code "33") (name "Net-(IC1A-D)") (class "Default")
      (node (ref "IC1") (pin "2") (pinfunction "D_2") (pintype "input"))
      (node (ref "IC1") (pin "8") (pinfunction "~{Q}_8") (pintype "output"))
      (node (ref "R12") (pin "1") (pinfunction "1_1") (pintype "passive"))
    )
    (net (code "34") (name "Net-(IC1A-Q)") (class "Default")
      (node (ref "IC1") (pin "12") (pinfunction "D_12") (pintype "input"))
      (node (ref "IC1") (pin "5") (pinfunction "Q_5") (pintype "output"))
      (node (ref "R14") (pin "1") (pinfunction "1_1") (pintype "passive"))
    )
    (net (code "35") (name "Net-(IC1A-~{Q})") (class "Default")
      (node (ref "IC1") (pin "6") (pinfunction "~{Q}_6") (pintype "output"))
      (node (ref "R13") (pin "1") (pinfunction "1_1") (pintype "passive"))
    )
    (net (code "36") (name "Net-(IC1B-Q)") (class "Default")
      (node (ref "IC1") (pin "9") (pinfunction "Q_9") (pintype "output"))
      (node (ref "R11") (pin "1") (pinfunction "1_1") (pintype "passive"))
    )
    (net (code "37") (name "Net-(IC2A-A)") (class "Default")
      (node (ref "C4") (pin "1") (pinfunction "1_1") (pintype "passive"))
      (node (ref "IC2") (pin "1") (pinfunction "A_1") (pintype "tri_state"))
      (node (ref "IC2") (pin "11") (pinfunction "A_11") (pintype "tri_state"))
      (node (ref "IC2") (pin "4") (pinfunction "A_4") (pintype "tri_state"))
      (node (ref "IC2") (pin "8") (pinfunction "A_8") (pintype "tri_state"))
      (node (ref "L2") (pin "2") (pinfunction "2_2") (pintype "passive"))
    )
    (net (code "38") (name "Net-(IC2A-B)") (class "Default")
      (node (ref "IC2") (pin "10") (pinfunction "B_10") (pintype "tri_state"))
      (node (ref "IC2") (pin "2") (pinfunction "B_2") (pintype "tri_state"))
      (node (ref "R15") (pin "2") (pinfunction "2_2") (pintype "passive"))
    )
    (net (code "39") (name "Net-(IC2A-C)") (class "Default")
      (node (ref "IC2") (pin "12") (pinfunction "C_12") (pintype "input"))
      (node (ref "IC2") (pin "13") (pinfunction "C_13") (pintype "input"))
      (node (ref "R14") (pin "2") (pinfunction "2_2") (pintype "passive"))
    )
    (net (code "40") (name "Net-(IC2B-B)") (class "Default")
      (node (ref "IC2") (pin "3") (pinfunction "B_3") (pintype "tri_state"))
      (node (ref "IC2") (pin "9") (pinfunction "B_9") (pintype "tri_state"))
      (node (ref "R16") (pin "2") (pinfunction "2_2") (pintype "passive"))
    )
    (net (code "41") (name "Net-(IC2B-C)") (class "Default")
      (node (ref "IC2") (pin "5") (pinfunction "C_5") (pintype "input"))
      (node (ref "IC2") (pin "6") (pinfunction "C_6") (pintype "input"))
      (node (ref "R13") (pin "2") (pinfunction "2_2") (pintype "passive"))
    )
    (net (code "42") (name "Net-(IC3A-A)") (class "Default")
      (node (ref "C5") (pin "1") (pinfunction "1_1") (pintype "passive"))
      (node (ref "IC3") (pin "1") (pinfunction "A_1") (pintype "tri_state"))
      (node (ref "IC3") (pin "11") (pinfunction "A_11") (pintype "tri_state"))
      (node (ref "IC3") (pin "4") (pinfunction "A_4") (pintype "tri_state"))
      (node (ref "IC3") (pin "8") (pinfunction "A_8") (pintype "tri_state"))
      (node (ref "L1") (pin "2") (pinfunction "2_2") (pintype "passive"))
    )
    (net (code "43") (name "Net-(IC3A-B)") (class "Default")
      (node (ref "IC3") (pin "10") (pinfunction "B_10") (pintype "tri_state"))
      (node (ref "IC3") (pin "2") (pinfunction "B_2") (pintype "tri_state"))
      (node (ref "R17") (pin "2") (pinfunction "2_2") (pintype "passive"))
    )
    (net (code "44") (name "Net-(IC3A-C)") (class "Default")
      (node (ref "IC3") (pin "12") (pinfunction "C_12") (pintype "input"))
      (node (ref "IC3") (pin "13") (pinfunction "C_13") (pintype "input"))
      (node (ref "R11") (pin "2") (pinfunction "2_2") (pintype "passive"))
    )
    (net (code "45") (name "Net-(IC3B-B)") (class "Default")
      (node (ref "IC3") (pin "3") (pinfunction "B_3") (pintype "tri_state"))
      (node (ref "IC3") (pin "9") (pinfunction "B_9") (pintype "tri_state"))
      (node (ref "R18") (pin "2") (pinfunction "2_2") (pintype "passive"))
    )
    (net (code "46") (name "Net-(IC3B-C)") (class "Default")
      (node (ref "IC3") (pin "5") (pinfunction "C_5") (pintype "input"))
      (node (ref "IC3") (pin "6") (pinfunction "C_6") (pintype "input"))
      (node (ref "R12") (pin "2") (pinfunction "2_2") (pintype "passive"))
    )
    (net (code "47") (name "Net-(IC4-Pad1)") (class "Default")
      (node (ref "IC4") (pin "1") (pinfunction "1_1") (pintype "passive"))
      (node (ref "R25") (pin "1") (pinfunction "1_1") (pintype "passive"))
      (node (ref "R32") (pin "2") (pinfunction "2_2") (pintype "passive"))
    )
    (net (code "48") (name "Net-(IC4-Pad2)") (class "Default")
      (node (ref "IC4") (pin "2") (pinfunction "2_2") (pintype "passive"))
      (node (ref "R23") (pin "1") (pinfunction "1_1") (pintype "passive"))
      (node (ref "R25") (pin "2") (pinfunction "2_2") (pintype "passive"))
    )
    (net (code "49") (name "Net-(IC4-Pad6)") (class "Default")
      (node (ref "IC4") (pin "6") (pinfunction "6_6") (pintype "passive"))
      (node (ref "R23") (pin "2") (pinfunction "2_2") (pintype "passive"))
      (node (ref "R27") (pin "2") (pinfunction "2_2") (pintype "passive"))
    )
    (net (code "50") (name "Net-(IC4-Pad7)") (class "Default")
      (node (ref "IC4") (pin "7") (pinfunction "7_7") (pintype "passive"))
      (node (ref "R27") (pin "1") (pinfunction "1_1") (pintype "passive"))
      (node (ref "R33") (pin "2") (pinfunction "2_2") (pintype "passive"))
    )
    (net (code "51") (name "Net-(IC5-Pad1)") (class "Default")
      (node (ref "IC5") (pin "1") (pinfunction "1_1") (pintype "passive"))
      (node (ref "R28") (pin "1") (pinfunction "1_1") (pintype "passive"))
      (node (ref "R34") (pin "2") (pinfunction "2_2") (pintype "passive"))
    )
    (net (code "52") (name "Net-(IC5-Pad2)") (class "Default")
      (node (ref "IC5") (pin "2") (pinfunction "2_2") (pintype "passive"))
      (node (ref "R24") (pin "1") (pinfunction "1_1") (pintype "passive"))
      (node (ref "R28") (pin "2") (pinfunction "2_2") (pintype "passive"))
    )
    (net (code "53") (name "Net-(IC5-Pad6)") (class "Default")
      (node (ref "IC5") (pin "6") (pinfunction "6_6") (pintype "passive"))
      (node (ref "R24") (pin "2") (pinfunction "2_2") (pintype "passive"))
      (node (ref "R30") (pin "2") (pinfunction "2_2") (pintype "passive"))
    )
    (net (code "54") (name "Net-(IC5-Pad7)") (class "Default")
      (node (ref "IC5") (pin "7") (pinfunction "7_7") (pintype "passive"))
      (node (ref "R30") (pin "1") (pinfunction "1_1") (pintype "passive"))
      (node (ref "R35") (pin "2") (pinfunction "2_2") (pintype "passive"))
    )
    (net (code "55") (name "Net-(IC7-Pad2)") (class "Default")
      (node (ref "IC7") (pin "2") (pinfunction "2_2") (pintype "passive"))
      (node (ref "R33") (pin "1") (pinfunction "1_1") (pintype "passive"))
      (node (ref "R36") (pin "2") (pinfunction "2_2") (pintype "passive"))
    )
    (net (code "56") (name "Net-(IC7-Pad3)") (class "Default")
      (node (ref "IC7") (pin "3") (pinfunction "3_3") (pintype "passive"))
      (node (ref "R32") (pin "1") (pinfunction "1_1") (pintype "passive"))
      (node (ref "R38") (pin "2") (pinfunction "2_2") (pintype "passive"))
    )
    (net (code "57") (name "Net-(IC7-Pad6)") (class "Default")
      (node (ref "IC7") (pin "6") (pinfunction "6_6") (pintype "passive"))
      (node (ref "R39") (pin "2") (pinfunction "2_2") (pintype "passive"))
      (node (ref "R40") (pin "2") (pinfunction "2_2") (pintype "passive"))
    )
    (net (code "58") (name "Net-(IC8-Pad2)") (class "Default")
      (node (ref "IC8") (pin "2") (pinfunction "2_2") (pintype "passive"))
      (node (ref "R35") (pin "1") (pinfunction "1_1") (pintype "passive"))
      (node (ref "R37") (pin "2") (pinfunction "2_2") (pintype "passive"))
    )
    (net (code "59") (name "Net-(IC8-Pad3)") (class "Default")
      (node (ref "IC8") (pin "3") (pinfunction "3_3") (pintype "passive"))
      (node (ref "R34") (pin "1") (pinfunction "1_1") (pintype "passive"))
      (node (ref "R41") (pin "2") (pinfunction "2_2") (pintype "passive"))
    )
    (net (code "60") (name "Net-(IC8-Pad6)") (class "Default")
      (node (ref "IC8") (pin "6") (pinfunction "6_6") (pintype "passive"))
      (node (ref "R42") (pin "2") (pinfunction "2_2") (pintype "passive"))
      (node (ref "R43") (pin "2") (pinfunction "2_2") (pintype "passive"))
    )
    (net (code "61") (name "Net-(JP2-Pad2)") (class "Default")
      (node (ref "JP2") (pin "2") (pinfunction "2_2") (pintype "passive"))
      (node (ref "X3") (pin "5") (pinfunction "5_5") (pintype "passive"))
      (node (ref "X4") (pin "2") (pinfunction "2_2") (pintype "passive"))
    )
    (net (code "62") (name "Net-(JP3-Pad2)") (class "Default")
      (node (ref "JP3") (pin "2") (pinfunction "2_2") (pintype "passive"))
      (node (ref "X4") (pin "5") (pinfunction "5_5") (pintype "passive"))
      (node (ref "X5") (pin "5") (pinfunction "5_5") (pintype "passive"))
    )
    (net (code "63") (name "Net-(L1-Pad1)") (class "Default")
      (node (ref "L1") (pin "1") (pinfunction "1_1") (pintype "passive"))
      (node (ref "L2") (pin "1") (pinfunction "1_1") (pintype "passive"))
      (node (ref "R10") (pin "2") (pinfunction "2_2") (pintype "passive"))
      (node (ref "R9") (pin "1") (pinfunction "1_1") (pintype "passive"))
    )
    (net (code "64") (name "Net-(LED1-PadA)") (class "Default")
      (node (ref "LED1") (pin "A") (pinfunction "A_A") (pintype "passive"))
      (node (ref "R31") (pin "2") (pinfunction "2_2") (pintype "passive"))
    )
    (net (code "65") (name "unconnected-(JP1-Pad2)") (class "Default")
      (node (ref "JP1") (pin "2") (pinfunction "2_2") (pintype "passive"))
    )
    (net (code "66") (name "unconnected-(X3-Pad2)") (class "Default")
      (node (ref "X3") (pin "2") (pinfunction "2_2") (pintype "passive"))
    )
    (net (code "67") (name "unconnected-(X3-Pad3)") (class "Default")
      (node (ref "X3") (pin "3") (pinfunction "3_3") (pintype "passive"))
    )
    (net (code "68") (name "unconnected-(X3-Pad4)") (class "Default")
      (node (ref "X3") (pin "4") (pinfunction "4_4") (pintype "passive"))
    )
    (net (code "69") (name "unconnected-(X4-Pad3)") (class "Default")
      (node (ref "X4") (pin "3") (pinfunction "3_3") (pintype "passive"))
    )
    (net (code "70") (name "unconnected-(X4-Pad4)") (class "Default")
      (node (ref "X4") (pin "4") (pinfunction "4_4") (pintype "passive"))
    )
    (net (code "71") (name "unconnected-(X5-Pad2)") (class "Default")
      (node (ref "X5") (pin "2") (pinfunction "2_2") (pintype "passive"))
    )
    (net (code "72") (name "unconnected-(X5-Pad3)") (class "Default")
      (node (ref "X5") (pin "3") (pinfunction "3_3") (pintype "passive"))
    )
    (net (code "73") (name "unconnected-(X5-Pad4)") (class "Default")
      (node (ref "X5") (pin "4") (pinfunction "4_4") (pintype "passive"))
    )
  )
)
